# power.net
KiCad netlist of a schematic drawn in Altium Designer
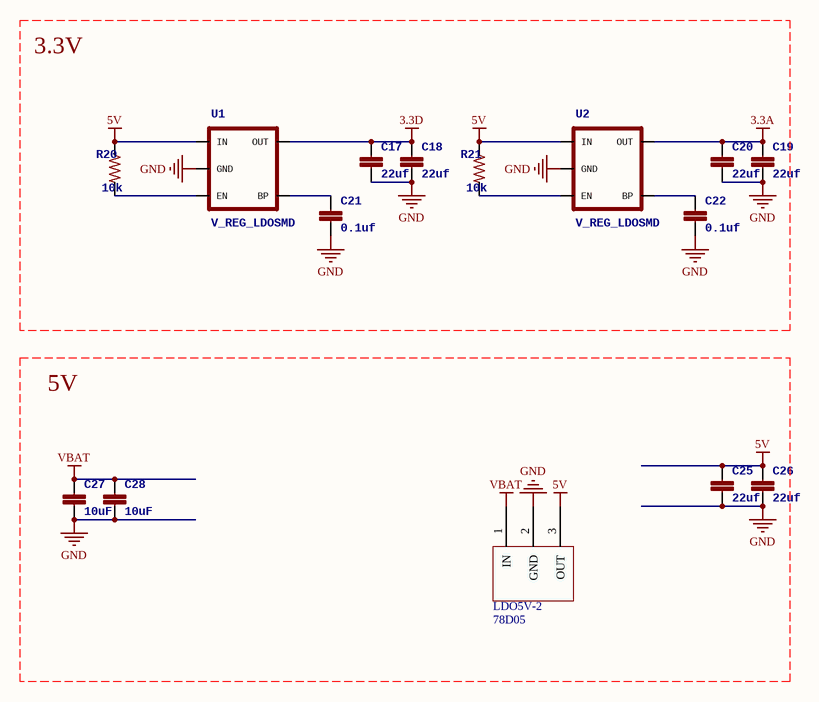
[diagram p0: power.SchDoc]

(export (version "E")
  (design (tool "Eeschema 10.0.6"))
  (components
    (comp (ref "C17")
      (value "22uf")
      (footprint "0805")
      (description "电容")
      (fields (field (name "PARTNO") "CC0402ZRY5V7BB104"))
      (libsource (lib "mcu_board") (part "CAP0402-CAP"))
    )
    (comp (ref "C18")
      (value "22uf")
      (footprint "0805")
      (description "电容")
      (fields (field (name "PARTNO") "CC0402ZRY5V7BB104"))
      (libsource (lib "mcu_board") (part "CAP0402-CAP"))
    )
    (comp (ref "C19")
      (value "22uf")
      (footprint "0805")
      (description "电容")
      (fields (field (name "PARTNO") "CC0402ZRY5V7BB104"))
      (libsource (lib "mcu_board") (part "CAP0402-CAP"))
    )
    (comp (ref "C20")
      (value "22uf")
      (footprint "0805")
      (description "电容")
      (fields (field (name "PARTNO") "CC0402ZRY5V7BB104"))
      (libsource (lib "mcu_board") (part "CAP0402-CAP"))
    )
    (comp (ref "C21")
      (value "0.1uf")
      (footprint "0603")
      (description "电容")
      (fields (field (name "PARTNO") "CC0402ZRY5V7BB104"))
      (libsource (lib "mcu_board") (part "CAP0402-CAP"))
    )
    (comp (ref "C22")
      (value "0.1uf")
      (footprint "0603")
      (description "电容")
      (fields (field (name "PARTNO") "CC0402ZRY5V7BB104"))
      (libsource (lib "mcu_board") (part "CAP0402-CAP"))
    )
    (comp (ref "C25")
      (value "22uf")
      (footprint "0805")
      (description "电容")
      (fields (field (name "PARTNO") "CC0402ZRY5V7BB104"))
      (libsource (lib "mcu_board") (part "CAP0402-CAP"))
    )
    (comp (ref "C26")
      (value "22uf")
      (footprint "0805")
      (description "电容")
      (fields (field (name "PARTNO") "CC0402ZRY5V7BB104"))
      (libsource (lib "mcu_board") (part "CAP0402-CAP"))
    )
    (comp (ref "C27")
      (value "10uF")
      (footprint "1206")
      (description "电容")
      (fields (field (name "PARTNO") "CC0402ZRY5V7BB104"))
      (libsource (lib "mcu_board") (part "CAP0402-CAP"))
    )
    (comp (ref "C28")
      (value "10uF")
      (footprint "1206")
      (description "电容")
      (fields (field (name "PARTNO") "CC0402ZRY5V7BB104"))
      (libsource (lib "mcu_board") (part "CAP0402-CAP"))
    )
    (comp (ref "LDO5V-2") (value "78D05") (footprint "TO-252-2L") (libsource (lib "sch") (part "78D05")))
    (comp (ref "R20")
      (value "10k")
      (footprint "0603")
      (description "电阻")
      (libsource (lib "mcu_board") (part "RESISTOR0402-RES"))
    )
    (comp (ref "R21")
      (value "10k")
      (footprint "0603")
      (description "电阻")
      (libsource (lib "mcu_board") (part "RESISTOR0402-RES"))
    )
    (comp (ref "U1")
      (value "V_REG_LDOSMD")
      (footprint "SOT23-5")
      (fields (field (name "PARTNO") "MIC5207-3.3YM5"))
      (libsource (lib "pixhawk2") (part "V_REG_LDOSMD"))
    )
    (comp (ref "U2")
      (value "V_REG_LDOSMD")
      (footprint "SOT23-5")
      (fields (field (name "PARTNO") "MIC5207-3.3YM5"))
      (libsource (lib "pixhawk2") (part "V_REG_LDOSMD"))
    )
  )
  (nets
    (net (code "1") (name "3.3A") (class "Default")
      (node (ref "C19") (pin "1") (pinfunction "1_1") (pintype "passive"))
      (node (ref "C20") (pin "1") (pinfunction "1_1") (pintype "passive"))
      (node (ref "U2") (pin "5") (pinfunction "OUT_5") (pintype "passive"))
    )
    (net (code "2") (name "3.3D") (class "Default")
      (node (ref "C17") (pin "1") (pinfunction "1_1") (pintype "passive"))
      (node (ref "C18") (pin "1") (pinfunction "1_1") (pintype "passive"))
      (node (ref "U1") (pin "5") (pinfunction "OUT_5") (pintype "passive"))
    )
    (net (code "3") (name "5V") (class "Default")
      (node (ref "C25") (pin "1") (pinfunction "1_1") (pintype "passive"))
      (node (ref "C26") (pin "1") (pinfunction "1_1") (pintype "passive"))
      (node (ref "LDO5V-2") (pin "3") (pinfunction "OUT_3") (pintype "passive"))
      (node (ref "R20") (pin "1") (pinfunction "1_1") (pintype "passive"))
      (node (ref "R21") (pin "1") (pinfunction "1_1") (pintype "passive"))
      (node (ref "U1") (pin "1") (pinfunction "IN_1") (pintype "passive"))
      (node (ref "U2") (pin "1") (pinfunction "IN_1") (pintype "passive"))
    )
    (net (code "4") (name "GND") (class "Default")
      (node (ref "C17") (pin "2") (pinfunction "2_2") (pintype "passive"))
      (node (ref "C18") (pin "2") (pinfunction "2_2") (pintype "passive"))
      (node (ref "C19") (pin "2") (pinfunction "2_2") (pintype "passive"))
      (node (ref "C20") (pin "2") (pinfunction "2_2") (pintype "passive"))
      (node (ref "C21") (pin "2") (pinfunction "2_2") (pintype "passive"))
      (node (ref "C22") (pin "2") (pinfunction "2_2") (pintype "passive"))
      (node (ref "C25") (pin "2") (pinfunction "2_2") (pintype "passive"))
      (node (ref "C26") (pin "2") (pinfunction "2_2") (pintype "passive"))
      (node (ref "C27") (pin "2") (pinfunction "2_2") (pintype "passive"))
      (node (ref "C28") (pin "2") (pinfunction "2_2") (pintype "passive"))
      (node (ref "LDO5V-2") (pin "2") (pinfunction "GND_2") (pintype "passive"))
      (node (ref "U1") (pin "2") (pinfunction "GND_2") (pintype "passive"))
      (node (ref "U2") (pin "2") (pinfunction "GND_2") (pintype "passive"))
    )
    (net (code "5") (name "Net-(U1-BP)") (class "Default")
      (node (ref "C21") (pin "1") (pinfunction "1_1") (pintype "passive"))
      (node (ref "U1") (pin "4") (pinfunction "BP_4") (pintype "passive"))
    )
    (net (code "6") (name "Net-(U1-EN)") (class "Default")
      (node (ref "R20") (pin "2") (pinfunction "2_2") (pintype "passive"))
      (node (ref "U1") (pin "3") (pinfunction "EN_3") (pintype "passive"))
    )
    (net (code "7") (name "Net-(U2-BP)") (class "Default")
      (node (ref "C22") (pin "1") (pinfunction "1_1") (pintype "passive"))
      (node (ref "U2") (pin "4") (pinfunction "BP_4") (pintype "passive"))
    )
    (net (code "8") (name "Net-(U2-EN)") (class "Default")
      (node (ref "R21") (pin "2") (pinfunction "2_2") (pintype "passive"))
      (node (ref "U2") (pin "3") (pinfunction "EN_3") (pintype "passive"))
    )
    (net (code "9") (name "VBAT") (class "Default")
      (node (ref "C27") (pin "1") (pinfunction "1_1") (pintype "passive"))
      (node (ref "C28") (pin "1") (pinfunction "1_1") (pintype "passive"))
      (node (ref "LDO5V-2") (pin "1") (pinfunction "IN_1") (pintype "passive"))
    )
  )
)
